# untitled.net
KiCad netlist of a schematic drawn in EAGLE
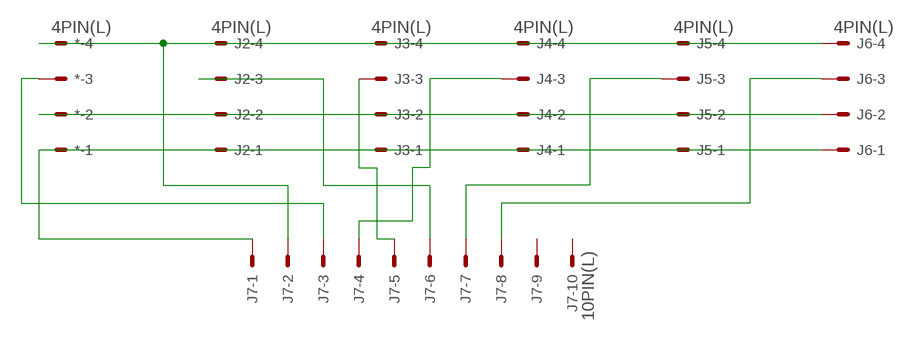
[diagram p0: schematic, sheet 1]

(export (version "E")
  (design (tool "Eeschema 10.0.6"))
  (components
    (comp (ref "*")
      (value "4PIN(L)")
      (footprint "eagle-import:4PL")
      (libsource (lib "eagle-import") (part "4PIN(L)"))
    )
    (comp (ref "J2")
      (value "4PIN(L)")
      (footprint "eagle-import:4PL")
      (libsource (lib "eagle-import") (part "4PIN(L)"))
    )
    (comp (ref "J3")
      (value "4PIN(L)")
      (footprint "eagle-import:4PL")
      (libsource (lib "eagle-import") (part "4PIN(L)"))
    )
    (comp (ref "J4")
      (value "4PIN(L)")
      (footprint "eagle-import:4PL")
      (libsource (lib "eagle-import") (part "4PIN(L)"))
    )
    (comp (ref "J5")
      (value "4PIN(L)")
      (footprint "eagle-import:4PL")
      (libsource (lib "eagle-import") (part "4PIN(L)"))
    )
    (comp (ref "J6")
      (value "4PIN(L)")
      (footprint "eagle-import:4PL")
      (libsource (lib "eagle-import") (part "4PIN(L)"))
    )
    (comp (ref "J7")
      (value "10PIN(L)")
      (footprint "eagle-import:10PL")
      (libsource (lib "eagle-import") (part "10PIN(L)"))
    )
  )
  (nets
    (net (code "1") (name "Net-(*A-S)") (class "Default")
      (node (ref "*") (pin "1") (pinfunction "S_1") (pintype "passive"))
      (node (ref "J2") (pin "1") (pinfunction "S_1") (pintype "passive"))
      (node (ref "J3") (pin "1") (pinfunction "S_1") (pintype "passive"))
      (node (ref "J4") (pin "1") (pinfunction "S_1") (pintype "passive"))
      (node (ref "J5") (pin "1") (pinfunction "S_1") (pintype "passive"))
      (node (ref "J6") (pin "1") (pinfunction "S_1") (pintype "passive"))
      (node (ref "J7") (pin "1") (pinfunction "S_1") (pintype "passive"))
    )
    (net (code "2") (name "Net-(*B-S)") (class "Default")
      (node (ref "*") (pin "2") (pinfunction "S_2") (pintype "passive"))
      (node (ref "J2") (pin "2") (pinfunction "S_2") (pintype "passive"))
      (node (ref "J3") (pin "2") (pinfunction "S_2") (pintype "passive"))
      (node (ref "J4") (pin "2") (pinfunction "S_2") (pintype "passive"))
      (node (ref "J5") (pin "2") (pinfunction "S_2") (pintype "passive"))
      (node (ref "J6") (pin "2") (pinfunction "S_2") (pintype "passive"))
    )
    (net (code "3") (name "Net-(*C-S)") (class "Default")
      (node (ref "*") (pin "3") (pinfunction "S_3") (pintype "passive"))
      (node (ref "J7") (pin "3") (pinfunction "S_3") (pintype "passive"))
    )
    (net (code "4") (name "Net-(*D-S)") (class "Default")
      (node (ref "*") (pin "4") (pinfunction "S_4") (pintype "passive"))
      (node (ref "J2") (pin "4") (pinfunction "S_4") (pintype "passive"))
      (node (ref "J3") (pin "4") (pinfunction "S_4") (pintype "passive"))
      (node (ref "J4") (pin "4") (pinfunction "S_4") (pintype "passive"))
      (node (ref "J5") (pin "4") (pinfunction "S_4") (pintype "passive"))
      (node (ref "J6") (pin "4") (pinfunction "S_4") (pintype "passive"))
      (node (ref "J7") (pin "2") (pinfunction "S_2") (pintype "passive"))
    )
    (net (code "5") (name "Net-(J2C-S)") (class "Default")
      (node (ref "J2") (pin "3") (pinfunction "S_3") (pintype "passive"))
      (node (ref "J7") (pin "6") (pinfunction "S_6") (pintype "passive"))
    )
    (net (code "6") (name "Net-(J3C-S)") (class "Default")
      (node (ref "J3") (pin "3") (pinfunction "S_3") (pintype "passive"))
      (node (ref "J7") (pin "5") (pinfunction "S_5") (pintype "passive"))
    )
    (net (code "7") (name "Net-(J4C-S)") (class "Default")
      (node (ref "J4") (pin "3") (pinfunction "S_3") (pintype "passive"))
      (node (ref "J7") (pin "4") (pinfunction "S_4") (pintype "passive"))
    )
    (net (code "8") (name "Net-(J5C-S)") (class "Default")
      (node (ref "J5") (pin "3") (pinfunction "S_3") (pintype "passive"))
      (node (ref "J7") (pin "7") (pinfunction "S_7") (pintype "passive"))
    )
    (net (code "9") (name "Net-(J6C-S)") (class "Default")
      (node (ref "J6") (pin "3") (pinfunction "S_3") (pintype "passive"))
      (node (ref "J7") (pin "8") (pinfunction "S_8") (pintype "passive"))
    )
    (net (code "10") (name "unconnected-(J7B-S-Pad10)") (class "Default")
      (node (ref "J7") (pin "10") (pinfunction "S_10") (pintype "passive"))
    )
    (net (code "11") (name "unconnected-(J7J-S-Pad9)") (class "Default")
      (node (ref "J7") (pin "9") (pinfunction "S_9") (pintype "passive"))
    )
  )
)
